# io_1.net
KiCad netlist of a schematic drawn in Altium Designer
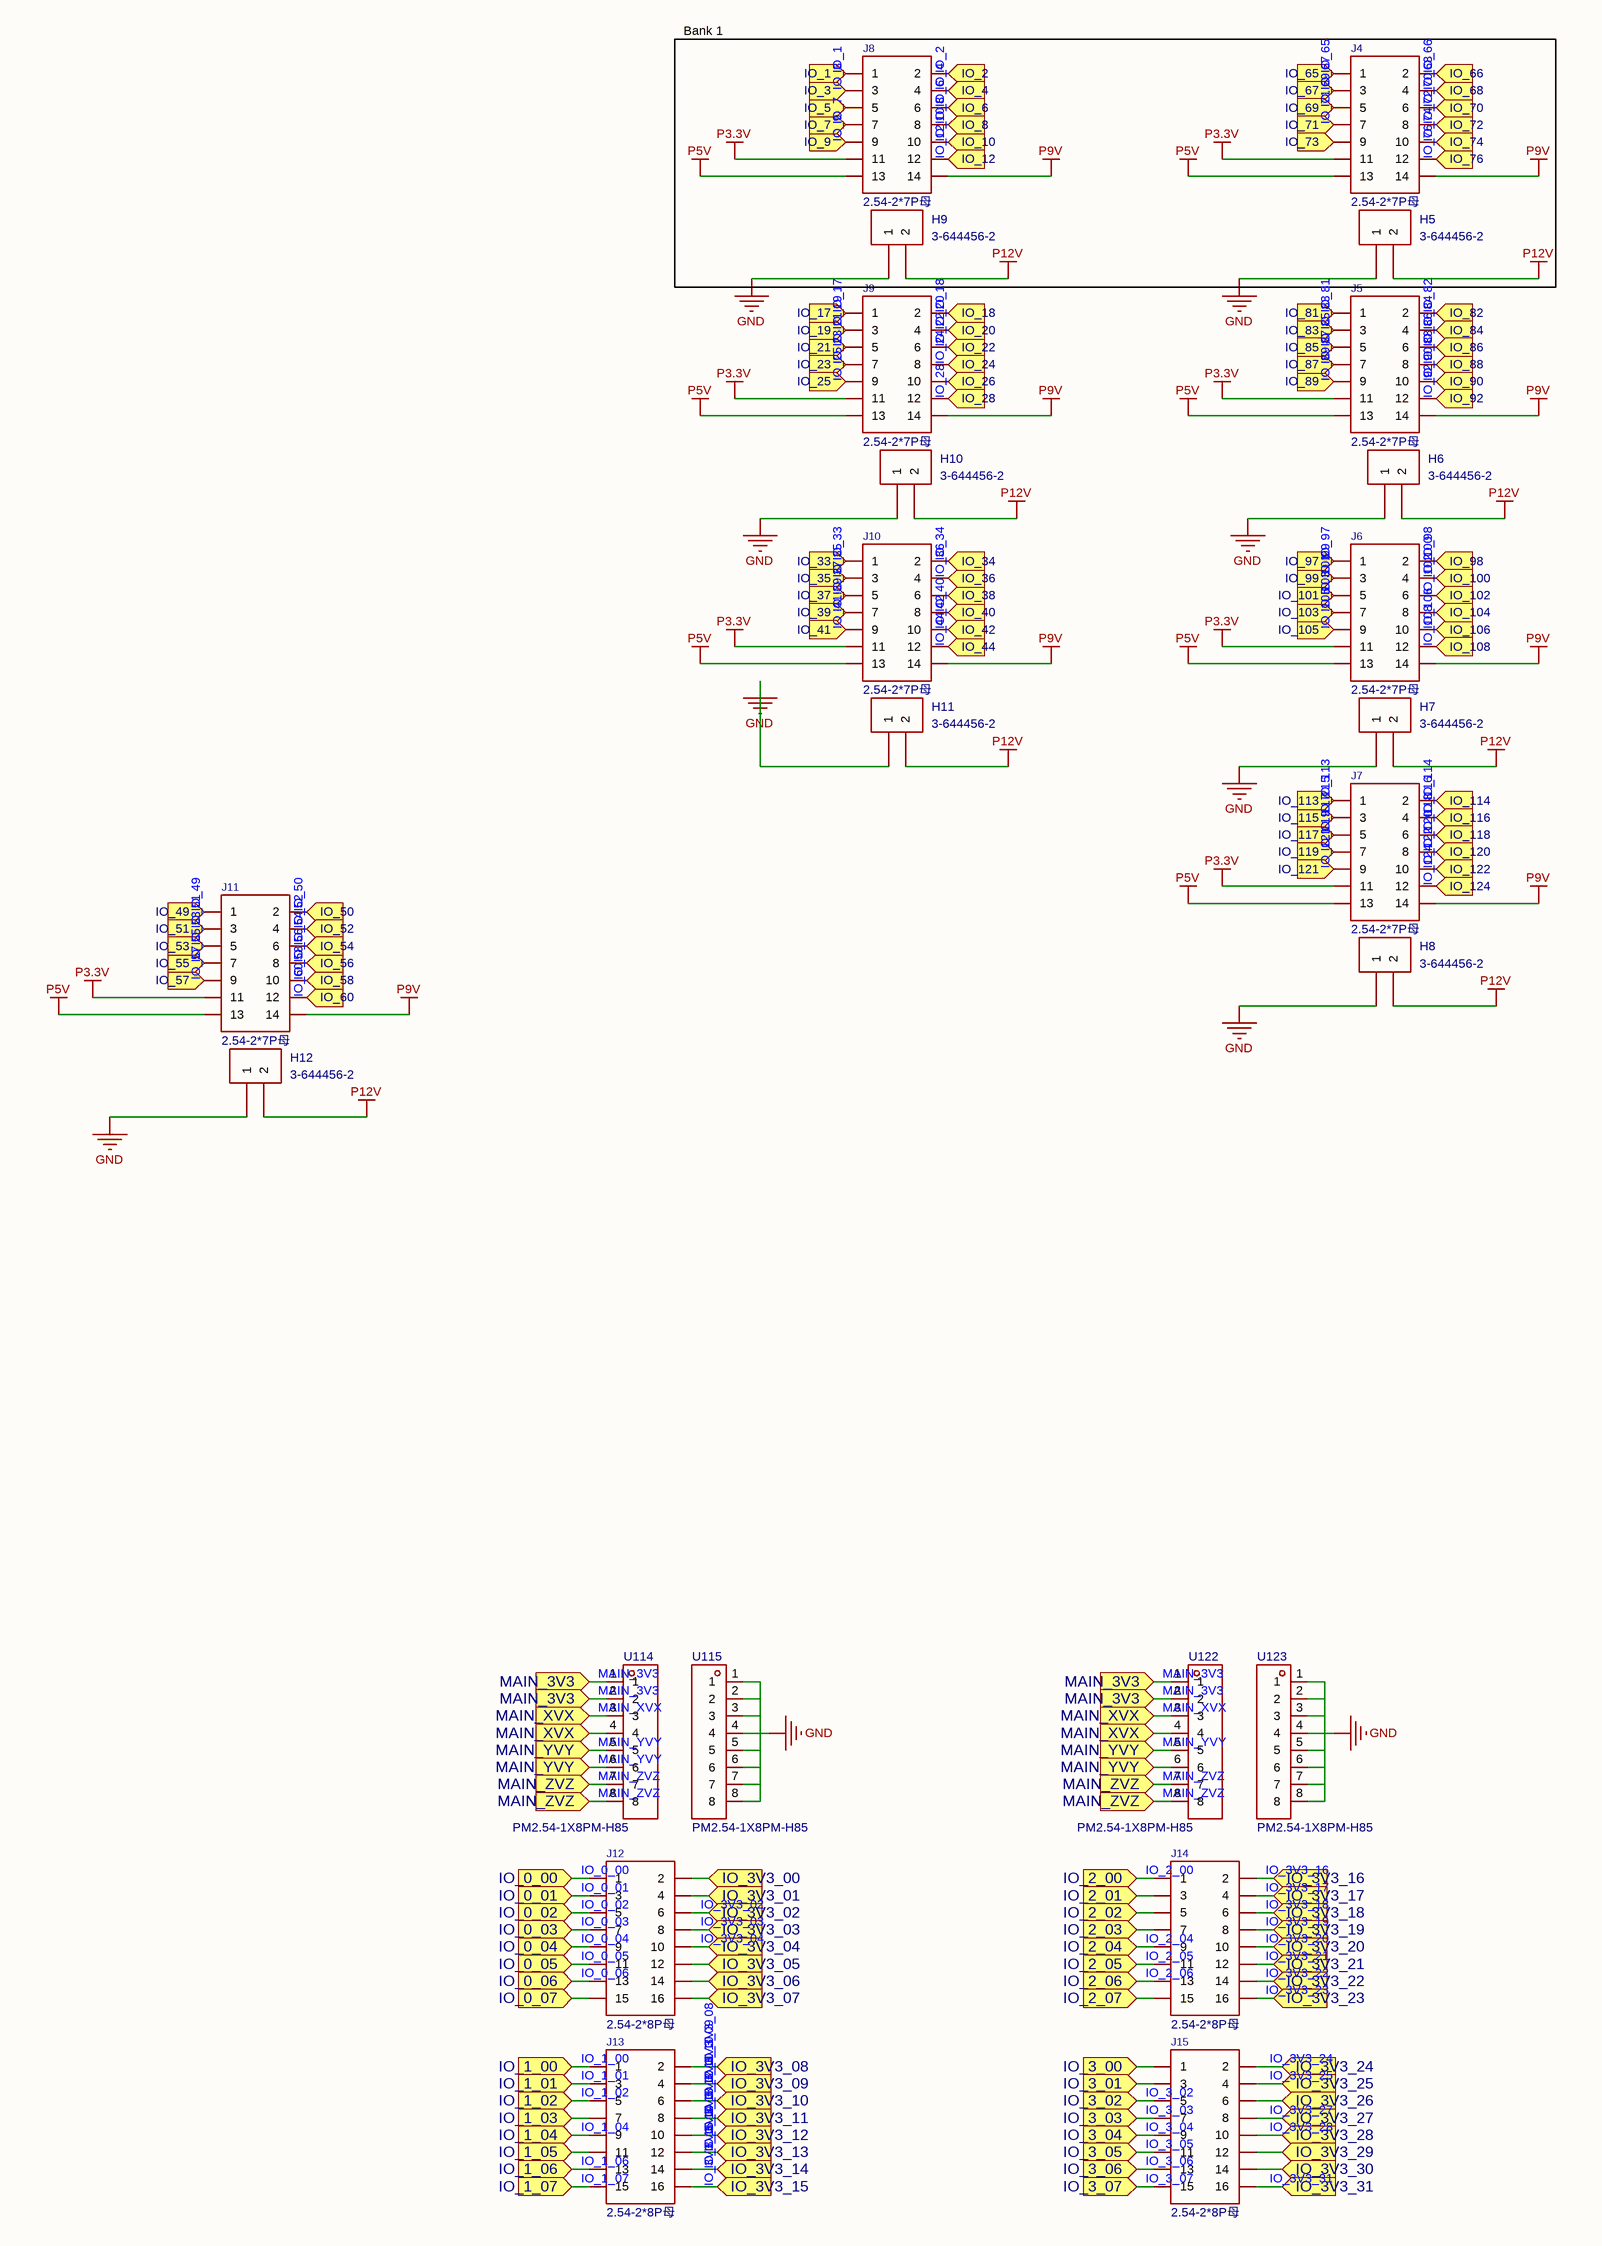
[diagram p0: io_1.schdoc]

(export (version "E")
  (design (tool "Eeschema 10.0.6"))
  (components
    (comp (ref "H5")
      (value "3-644456-2")
      (footprint "HDR-TH_2P-P2.54-V-M-1")
      (fields (field (name "MANUFACTURER") "TE Connectivity(泰科电子)"))
      (libsource (lib "altium-import") (part "root_1_3-644456-2_"))
    )
    (comp (ref "H6")
      (value "3-644456-2")
      (footprint "HDR-TH_2P-P2.54-V-M-1")
      (fields (field (name "MANUFACTURER") "TE Connectivity(泰科电子)"))
      (libsource (lib "altium-import") (part "root_1_3-644456-2_"))
    )
    (comp (ref "H7")
      (value "3-644456-2")
      (footprint "HDR-TH_2P-P2.54-V-M-1")
      (fields (field (name "MANUFACTURER") "TE Connectivity(泰科电子)"))
      (libsource (lib "altium-import") (part "root_1_3-644456-2_"))
    )
    (comp (ref "H8")
      (value "3-644456-2")
      (footprint "HDR-TH_2P-P2.54-V-M-1")
      (fields (field (name "MANUFACTURER") "TE Connectivity(泰科电子)"))
      (libsource (lib "altium-import") (part "root_1_3-644456-2_"))
    )
    (comp (ref "H9")
      (value "3-644456-2")
      (footprint "HDR-TH_2P-P2.54-V-M-1")
      (fields (field (name "MANUFACTURER") "TE Connectivity(泰科电子)"))
      (libsource (lib "altium-import") (part "root_1_3-644456-2_"))
    )
    (comp (ref "H10")
      (value "3-644456-2")
      (footprint "HDR-TH_2P-P2.54-V-M-1")
      (fields (field (name "MANUFACTURER") "TE Connectivity(泰科电子)"))
      (libsource (lib "altium-import") (part "root_1_3-644456-2_"))
    )
    (comp (ref "H11")
      (value "3-644456-2")
      (footprint "HDR-TH_2P-P2.54-V-M-1")
      (fields (field (name "MANUFACTURER") "TE Connectivity(泰科电子)"))
      (libsource (lib "altium-import") (part "root_1_3-644456-2_"))
    )
    (comp (ref "H12")
      (value "3-644456-2")
      (footprint "HDR-TH_2P-P2.54-V-M-1")
      (fields (field (name "MANUFACTURER") "TE Connectivity(泰科电子)"))
      (libsource (lib "altium-import") (part "root_1_3-644456-2_"))
    )
    (comp (ref "J4")
      (value "2.54-2*7P母")
      (footprint "HDR-TH_14P-P2.54-V-F-R2-C7-S2.54-1")
      (fields (field (name "MANUFACTURER") "BOOMELE(博穆精密)"))
      (libsource (lib "altium-import") (part "root_0_2.54-2*7P母_"))
    )
    (comp (ref "J5")
      (value "2.54-2*7P母")
      (footprint "HDR-TH_14P-P2.54-V-F-R2-C7-S2.54-1")
      (fields (field (name "MANUFACTURER") "BOOMELE(博穆精密)"))
      (libsource (lib "altium-import") (part "root_0_2.54-2*7P母_"))
    )
    (comp (ref "J6")
      (value "2.54-2*7P母")
      (footprint "HDR-TH_14P-P2.54-V-F-R2-C7-S2.54-1")
      (fields (field (name "MANUFACTURER") "BOOMELE(博穆精密)"))
      (libsource (lib "altium-import") (part "root_0_2.54-2*7P母_"))
    )
    (comp (ref "J7")
      (value "2.54-2*7P母")
      (footprint "HDR-TH_14P-P2.54-V-F-R2-C7-S2.54-1")
      (fields (field (name "MANUFACTURER") "BOOMELE(博穆精密)"))
      (libsource (lib "altium-import") (part "root_0_2.54-2*7P母_"))
    )
    (comp (ref "J8")
      (value "2.54-2*7P母")
      (footprint "HDR-TH_14P-P2.54-V-F-R2-C7-S2.54-1")
      (fields (field (name "MANUFACTURER") "BOOMELE(博穆精密)"))
      (libsource (lib "altium-import") (part "root_0_2.54-2*7P母_"))
    )
    (comp (ref "J9")
      (value "2.54-2*7P母")
      (footprint "HDR-TH_14P-P2.54-V-F-R2-C7-S2.54-1")
      (fields (field (name "MANUFACTURER") "BOOMELE(博穆精密)"))
      (libsource (lib "altium-import") (part "root_0_2.54-2*7P母_"))
    )
    (comp (ref "J10")
      (value "2.54-2*7P母")
      (footprint "HDR-TH_14P-P2.54-V-F-R2-C7-S2.54-1")
      (fields (field (name "MANUFACTURER") "BOOMELE(博穆精密)"))
      (libsource (lib "altium-import") (part "root_0_2.54-2*7P母_"))
    )
    (comp (ref "J11")
      (value "2.54-2*7P母")
      (footprint "HDR-TH_14P-P2.54-V-F-R2-C7-S2.54-1")
      (fields (field (name "MANUFACTURER") "BOOMELE(博穆精密)"))
      (libsource (lib "altium-import") (part "root_0_2.54-2*7P母_"))
    )
    (comp (ref "J12")
      (value "2.54-2*8P母")
      (footprint "HDR-TH_16P-P2.54-V-F-R2-C8-S2.54")
      (fields (field (name "MANUFACTURER") "BOOMELE(博穆精密)"))
      (libsource (lib "altium-import") (part "root_0_2.54-2*8P母_"))
    )
    (comp (ref "J13")
      (value "2.54-2*8P母")
      (footprint "HDR-TH_16P-P2.54-V-F-R2-C8-S2.54")
      (fields (field (name "MANUFACTURER") "BOOMELE(博穆精密)"))
      (libsource (lib "altium-import") (part "root_0_2.54-2*8P母_"))
    )
    (comp (ref "J14")
      (value "2.54-2*8P母")
      (footprint "HDR-TH_16P-P2.54-V-F-R2-C8-S2.54")
      (fields (field (name "MANUFACTURER") "BOOMELE(博穆精密)"))
      (libsource (lib "altium-import") (part "root_0_2.54-2*8P母_"))
    )
    (comp (ref "J15")
      (value "2.54-2*8P母")
      (footprint "HDR-TH_16P-P2.54-V-F-R2-C8-S2.54")
      (fields (field (name "MANUFACTURER") "BOOMELE(博穆精密)"))
      (libsource (lib "altium-import") (part "root_0_2.54-2*8P母_"))
    )
    (comp (ref "U114")
      (value "PM2.54-1X8PM-H85")
      (footprint "HDR-TH_8P-P2.54-V-F")
      (fields (field (name "MANUFACTURER") "JXTCONN(聚兴泰)"))
      (libsource (lib "altium-import") (part "root_0_PM2.54-1X8PM-H85_"))
    )
    (comp (ref "U115")
      (value "PM2.54-1X8PM-H85")
      (footprint "HDR-TH_8P-P2.54-V-F")
      (fields (field (name "MANUFACTURER") "JXTCONN(聚兴泰)"))
      (libsource (lib "altium-import") (part "root_0_mirrored_PM2.54-1X8PM-H85_"))
    )
    (comp (ref "U122")
      (value "PM2.54-1X8PM-H85")
      (footprint "HDR-TH_8P-P2.54-V-F")
      (fields (field (name "MANUFACTURER") "JXTCONN(聚兴泰)"))
      (libsource (lib "altium-import") (part "root_0_PM2.54-1X8PM-H85_"))
    )
    (comp (ref "U123")
      (value "PM2.54-1X8PM-H85")
      (footprint "HDR-TH_8P-P2.54-V-F")
      (fields (field (name "MANUFACTURER") "JXTCONN(聚兴泰)"))
      (libsource (lib "altium-import") (part "root_0_mirrored_PM2.54-1X8PM-H85_"))
    )
  )
  (nets
    (net (code "1") (name "/IO_0_00") (class "Default")
      (node (ref "J12") (pin "1") (pinfunction "1_1") (pintype "passive"))
    )
    (net (code "2") (name "/IO_0_01") (class "Default")
      (node (ref "J12") (pin "3") (pinfunction "3_3") (pintype "passive"))
    )
    (net (code "3") (name "/IO_0_02") (class "Default")
      (node (ref "J12") (pin "5") (pinfunction "5_5") (pintype "passive"))
    )
    (net (code "4") (name "/IO_0_03") (class "Default")
      (node (ref "J12") (pin "7") (pinfunction "7_7") (pintype "passive"))
    )
    (net (code "5") (name "/IO_0_04") (class "Default")
      (node (ref "J12") (pin "9") (pinfunction "9_9") (pintype "passive"))
    )
    (net (code "6") (name "/IO_0_05") (class "Default")
      (node (ref "J12") (pin "11") (pinfunction "11_11") (pintype "passive"))
    )
    (net (code "7") (name "/IO_0_06") (class "Default")
      (node (ref "J12") (pin "13") (pinfunction "13_13") (pintype "passive"))
    )
    (net (code "8") (name "/IO_0_07") (class "Default")
      (node (ref "J12") (pin "15") (pinfunction "15_15") (pintype "passive"))
    )
    (net (code "9") (name "/IO_1") (class "Default")
      (node (ref "J8") (pin "1") (pinfunction "1_1") (pintype "passive"))
    )
    (net (code "10") (name "/IO_1_00") (class "Default")
      (node (ref "J13") (pin "1") (pinfunction "1_1") (pintype "passive"))
    )
    (net (code "11") (name "/IO_1_01") (class "Default")
      (node (ref "J13") (pin "3") (pinfunction "3_3") (pintype "passive"))
    )
    (net (code "12") (name "/IO_1_02") (class "Default")
      (node (ref "J13") (pin "5") (pinfunction "5_5") (pintype "passive"))
    )
    (net (code "13") (name "/IO_1_03") (class "Default")
      (node (ref "J13") (pin "7") (pinfunction "7_7") (pintype "passive"))
    )
    (net (code "14") (name "/IO_1_04") (class "Default")
      (node (ref "J13") (pin "9") (pinfunction "9_9") (pintype "passive"))
    )
    (net (code "15") (name "/IO_1_05") (class "Default")
      (node (ref "J13") (pin "11") (pinfunction "11_11") (pintype "passive"))
    )
    (net (code "16") (name "/IO_1_06") (class "Default")
      (node (ref "J13") (pin "13") (pinfunction "13_13") (pintype "passive"))
    )
    (net (code "17") (name "/IO_1_07") (class "Default")
      (node (ref "J13") (pin "15") (pinfunction "15_15") (pintype "passive"))
    )
    (net (code "18") (name "/IO_2") (class "Default")
      (node (ref "J8") (pin "2") (pinfunction "2_2") (pintype "passive"))
    )
    (net (code "19") (name "/IO_2_00") (class "Default")
      (node (ref "J14") (pin "1") (pinfunction "1_1") (pintype "passive"))
    )
    (net (code "20") (name "/IO_2_01") (class "Default")
      (node (ref "J14") (pin "3") (pinfunction "3_3") (pintype "passive"))
    )
    (net (code "21") (name "/IO_2_02") (class "Default")
      (node (ref "J14") (pin "5") (pinfunction "5_5") (pintype "passive"))
    )
    (net (code "22") (name "/IO_2_03") (class "Default")
      (node (ref "J14") (pin "7") (pinfunction "7_7") (pintype "passive"))
    )
    (net (code "23") (name "/IO_2_04") (class "Default")
      (node (ref "J14") (pin "9") (pinfunction "9_9") (pintype "passive"))
    )
    (net (code "24") (name "/IO_2_05") (class "Default")
      (node (ref "J14") (pin "11") (pinfunction "11_11") (pintype "passive"))
    )
    (net (code "25") (name "/IO_2_06") (class "Default")
      (node (ref "J14") (pin "13") (pinfunction "13_13") (pintype "passive"))
    )
    (net (code "26") (name "/IO_2_07") (class "Default")
      (node (ref "J14") (pin "15") (pinfunction "15_15") (pintype "passive"))
    )
    (net (code "27") (name "/IO_3") (class "Default")
      (node (ref "J8") (pin "3") (pinfunction "3_3") (pintype "passive"))
    )
    (net (code "28") (name "/IO_3V3_00") (class "Default")
      (node (ref "J12") (pin "2") (pinfunction "2_2") (pintype "passive"))
    )
    (net (code "29") (name "/IO_3V3_01") (class "Default")
      (node (ref "J12") (pin "4") (pinfunction "4_4") (pintype "passive"))
    )
    (net (code "30") (name "/IO_3V3_02") (class "Default")
      (node (ref "J12") (pin "6") (pinfunction "6_6") (pintype "passive"))
    )
    (net (code "31") (name "/IO_3V3_03") (class "Default")
      (node (ref "J12") (pin "8") (pinfunction "8_8") (pintype "passive"))
    )
    (net (code "32") (name "/IO_3V3_04") (class "Default")
      (node (ref "J12") (pin "10") (pinfunction "10_10") (pintype "passive"))
    )
    (net (code "33") (name "/IO_3V3_05") (class "Default")
      (node (ref "J12") (pin "12") (pinfunction "12_12") (pintype "passive"))
    )
    (net (code "34") (name "/IO_3V3_06") (class "Default")
      (node (ref "J12") (pin "14") (pinfunction "14_14") (pintype "passive"))
    )
    (net (code "35") (name "/IO_3V3_07") (class "Default")
      (node (ref "J12") (pin "16") (pinfunction "16_16") (pintype "passive"))
    )
    (net (code "36") (name "/IO_3V3_08") (class "Default")
      (node (ref "J13") (pin "2") (pinfunction "2_2") (pintype "passive"))
    )
    (net (code "37") (name "/IO_3V3_09") (class "Default")
      (node (ref "J13") (pin "4") (pinfunction "4_4") (pintype "passive"))
    )
    (net (code "38") (name "/IO_3V3_10") (class "Default")
      (node (ref "J13") (pin "6") (pinfunction "6_6") (pintype "passive"))
    )
    (net (code "39") (name "/IO_3V3_11") (class "Default")
      (node (ref "J13") (pin "8") (pinfunction "8_8") (pintype "passive"))
    )
    (net (code "40") (name "/IO_3V3_12") (class "Default")
      (node (ref "J13") (pin "10") (pinfunction "10_10") (pintype "passive"))
    )
    (net (code "41") (name "/IO_3V3_13") (class "Default")
      (node (ref "J13") (pin "12") (pinfunction "12_12") (pintype "passive"))
    )
    (net (code "42") (name "/IO_3V3_14") (class "Default")
      (node (ref "J13") (pin "14") (pinfunction "14_14") (pintype "passive"))
    )
    (net (code "43") (name "/IO_3V3_15") (class "Default")
      (node (ref "J13") (pin "16") (pinfunction "16_16") (pintype "passive"))
    )
    (net (code "44") (name "/IO_3V3_16") (class "Default")
      (node (ref "J14") (pin "2") (pinfunction "2_2") (pintype "passive"))
    )
    (net (code "45") (name "/IO_3V3_17") (class "Default")
      (node (ref "J14") (pin "4") (pinfunction "4_4") (pintype "passive"))
    )
    (net (code "46") (name "/IO_3V3_18") (class "Default")
      (node (ref "J14") (pin "6") (pinfunction "6_6") (pintype "passive"))
    )
    (net (code "47") (name "/IO_3V3_19") (class "Default")
      (node (ref "J14") (pin "8") (pinfunction "8_8") (pintype "passive"))
    )
    (net (code "48") (name "/IO_3V3_20") (class "Default")
      (node (ref "J14") (pin "10") (pinfunction "10_10") (pintype "passive"))
    )
    (net (code "49") (name "/IO_3V3_21") (class "Default")
      (node (ref "J14") (pin "12") (pinfunction "12_12") (pintype "passive"))
    )
    (net (code "50") (name "/IO_3V3_22") (class "Default")
      (node (ref "J14") (pin "14") (pinfunction "14_14") (pintype "passive"))
    )
    (net (code "51") (name "/IO_3V3_23") (class "Default")
      (node (ref "J14") (pin "16") (pinfunction "16_16") (pintype "passive"))
    )
    (net (code "52") (name "/IO_3V3_24") (class "Default")
      (node (ref "J15") (pin "2") (pinfunction "2_2") (pintype "passive"))
    )
    (net (code "53") (name "/IO_3V3_25") (class "Default")
      (node (ref "J15") (pin "4") (pinfunction "4_4") (pintype "passive"))
    )
    (net (code "54") (name "/IO_3V3_26") (class "Default")
      (node (ref "J15") (pin "6") (pinfunction "6_6") (pintype "passive"))
    )
    (net (code "55") (name "/IO_3V3_27") (class "Default")
      (node (ref "J15") (pin "8") (pinfunction "8_8") (pintype "passive"))
    )
    (net (code "56") (name "/IO_3V3_28") (class "Default")
      (node (ref "J15") (pin "10") (pinfunction "10_10") (pintype "passive"))
    )
    (net (code "57") (name "/IO_3V3_29") (class "Default")
      (node (ref "J15") (pin "12") (pinfunction "12_12") (pintype "passive"))
    )
    (net (code "58") (name "/IO_3V3_30") (class "Default")
      (node (ref "J15") (pin "14") (pinfunction "14_14") (pintype "passive"))
    )
    (net (code "59") (name "/IO_3V3_31") (class "Default")
      (node (ref "J15") (pin "16") (pinfunction "16_16") (pintype "passive"))
    )
    (net (code "60") (name "/IO_3_00") (class "Default")
      (node (ref "J15") (pin "1") (pinfunction "1_1") (pintype "passive"))
    )
    (net (code "61") (name "/IO_3_01") (class "Default")
      (node (ref "J15") (pin "3") (pinfunction "3_3") (pintype "passive"))
    )
    (net (code "62") (name "/IO_3_02") (class "Default")
      (node (ref "J15") (pin "5") (pinfunction "5_5") (pintype "passive"))
    )
    (net (code "63") (name "/IO_3_03") (class "Default")
      (node (ref "J15") (pin "7") (pinfunction "7_7") (pintype "passive"))
    )
    (net (code "64") (name "/IO_3_04") (class "Default")
      (node (ref "J15") (pin "9") (pinfunction "9_9") (pintype "passive"))
    )
    (net (code "65") (name "/IO_3_05") (class "Default")
      (node (ref "J15") (pin "11") (pinfunction "11_11") (pintype "passive"))
    )
    (net (code "66") (name "/IO_3_06") (class "Default")
      (node (ref "J15") (pin "13") (pinfunction "13_13") (pintype "passive"))
    )
    (net (code "67") (name "/IO_3_07") (class "Default")
      (node (ref "J15") (pin "15") (pinfunction "15_15") (pintype "passive"))
    )
    (net (code "68") (name "/IO_4") (class "Default")
      (node (ref "J8") (pin "4") (pinfunction "4_4") (pintype "passive"))
    )
    (net (code "69") (name "/IO_5") (class "Default")
      (node (ref "J8") (pin "5") (pinfunction "5_5") (pintype "passive"))
    )
    (net (code "70") (name "/IO_6") (class "Default")
      (node (ref "J8") (pin "6") (pinfunction "6_6") (pintype "passive"))
    )
    (net (code "71") (name "/IO_7") (class "Default")
      (node (ref "J8") (pin "7") (pinfunction "7_7") (pintype "passive"))
    )
    (net (code "72") (name "/IO_8") (class "Default")
      (node (ref "J8") (pin "8") (pinfunction "8_8") (pintype "passive"))
    )
    (net (code "73") (name "/IO_9") (class "Default")
      (node (ref "J8") (pin "9") (pinfunction "9_9") (pintype "passive"))
    )
    (net (code "74") (name "/IO_10") (class "Default")
      (node (ref "J8") (pin "10") (pinfunction "10_10") (pintype "passive"))
    )
    (net (code "75") (name "/IO_12") (class "Default")
      (node (ref "J8") (pin "12") (pinfunction "12_12") (pintype "passive"))
    )
    (net (code "76") (name "/IO_17") (class "Default")
      (node (ref "J9") (pin "1") (pinfunction "1_1") (pintype "passive"))
    )
    (net (code "77") (name "/IO_18") (class "Default")
      (node (ref "J9") (pin "2") (pinfunction "2_2") (pintype "passive"))
    )
    (net (code "78") (name "/IO_19") (class "Default")
      (node (ref "J9") (pin "3") (pinfunction "3_3") (pintype "passive"))
    )
    (net (code "79") (name "/IO_20") (class "Default")
      (node (ref "J9") (pin "4") (pinfunction "4_4") (pintype "passive"))
    )
    (net (code "80") (name "/IO_21") (class "Default")
      (node (ref "J9") (pin "5") (pinfunction "5_5") (pintype "passive"))
    )
    (net (code "81") (name "/IO_22") (class "Default")
      (node (ref "J9") (pin "6") (pinfunction "6_6") (pintype "passive"))
    )
    (net (code "82") (name "/IO_23") (class "Default")
      (node (ref "J9") (pin "7") (pinfunction "7_7") (pintype "passive"))
    )
    (net (code "83") (name "/IO_24") (class "Default")
      (node (ref "J9") (pin "8") (pinfunction "8_8") (pintype "passive"))
    )
    (net (code "84") (name "/IO_25") (class "Default")
      (node (ref "J9") (pin "9") (pinfunction "9_9") (pintype "passive"))
    )
    (net (code "85") (name "/IO_26") (class "Default")
      (node (ref "J9") (pin "10") (pinfunction "10_10") (pintype "passive"))
    )
    (net (code "86") (name "/IO_28") (class "Default")
      (node (ref "J9") (pin "12") (pinfunction "12_12") (pintype "passive"))
    )
    (net (code "87") (name "/IO_33") (class "Default")
      (node (ref "J10") (pin "1") (pinfunction "1_1") (pintype "passive"))
    )
    (net (code "88") (name "/IO_34") (class "Default")
      (node (ref "J10") (pin "2") (pinfunction "2_2") (pintype "passive"))
    )
    (net (code "89") (name "/IO_35") (class "Default")
      (node (ref "J10") (pin "3") (pinfunction "3_3") (pintype "passive"))
    )
    (net (code "90") (name "/IO_36") (class "Default")
      (node (ref "J10") (pin "4") (pinfunction "4_4") (pintype "passive"))
    )
    (net (code "91") (name "/IO_37") (class "Default")
      (node (ref "J10") (pin "5") (pinfunction "5_5") (pintype "passive"))
    )
    (net (code "92") (name "/IO_38") (class "Default")
      (node (ref "J10") (pin "6") (pinfunction "6_6") (pintype "passive"))
    )
    (net (code "93") (name "/IO_39") (class "Default")
      (node (ref "J10") (pin "7") (pinfunction "7_7") (pintype "passive"))
    )
    (net (code "94") (name "/IO_40") (class "Default")
      (node (ref "J10") (pin "8") (pinfunction "8_8") (pintype "passive"))
    )
    (net (code "95") (name "/IO_41") (class "Default")
      (node (ref "J10") (pin "9") (pinfunction "9_9") (pintype "passive"))
    )
    (net (code "96") (name "/IO_42") (class "Default")
      (node (ref "J10") (pin "10") (pinfunction "10_10") (pintype "passive"))
    )
    (net (code "97") (name "/IO_44") (class "Default")
      (node (ref "J10") (pin "12") (pinfunction "12_12") (pintype "passive"))
    )
    (net (code "98") (name "/IO_49") (class "Default")
      (node (ref "J11") (pin "1") (pinfunction "1_1") (pintype "passive"))
    )
    (net (code "99") (name "/IO_50") (class "Default")
      (node (ref "J11") (pin "2") (pinfunction "2_2") (pintype "passive"))
    )
    (net (code "100") (name "/IO_51") (class "Default")
      (node (ref "J11") (pin "3") (pinfunction "3_3") (pintype "passive"))
    )
    (net (code "101") (name "/IO_52") (class "Default")
      (node (ref "J11") (pin "4") (pinfunction "4_4") (pintype "passive"))
    )
    (net (code "102") (name "/IO_53") (class "Default")
      (node (ref "J11") (pin "5") (pinfunction "5_5") (pintype "passive"))
    )
    (net (code "103") (name "/IO_54") (class "Default")
      (node (ref "J11") (pin "6") (pinfunction "6_6") (pintype "passive"))
    )
    (net (code "104") (name "/IO_55") (class "Default")
      (node (ref "J11") (pin "7") (pinfunction "7_7") (pintype "passive"))
    )
    (net (code "105") (name "/IO_56") (class "Default")
      (node (ref "J11") (pin "8") (pinfunction "8_8") (pintype "passive"))
    )
    (net (code "106") (name "/IO_57") (class "Default")
      (node (ref "J11") (pin "9") (pinfunction "9_9") (pintype "passive"))
    )
    (net (code "107") (name "/IO_58") (class "Default")
      (node (ref "J11") (pin "10") (pinfunction "10_10") (pintype "passive"))
    )
    (net (code "108") (name "/IO_60") (class "Default")
      (node (ref "J11") (pin "12") (pinfunction "12_12") (pintype "passive"))
    )
    (net (code "109") (name "/IO_65") (class "Default")
      (node (ref "J4") (pin "1") (pinfunction "1_1") (pintype "passive"))
    )
    (net (code "110") (name "/IO_66") (class "Default")
      (node (ref "J4") (pin "2") (pinfunction "2_2") (pintype "passive"))
    )
    (net (code "111") (name "/IO_67") (class "Default")
      (node (ref "J4") (pin "3") (pinfunction "3_3") (pintype "passive"))
    )
    (net (code "112") (name "/IO_68") (class "Default")
      (node (ref "J4") (pin "4") (pinfunction "4_4") (pintype "passive"))
    )
    (net (code "113") (name "/IO_69") (class "Default")
      (node (ref "J4") (pin "5") (pinfunction "5_5") (pintype "passive"))
    )
    (net (code "114") (name "/IO_70") (class "Default")
      (node (ref "J4") (pin "6") (pinfunction "6_6") (pintype "passive"))
    )
    (net (code "115") (name "/IO_71") (class "Default")
      (node (ref "J4") (pin "7") (pinfunction "7_7") (pintype "passive"))
    )
    (net (code "116") (name "/IO_72") (class "Default")
      (node (ref "J4") (pin "8") (pinfunction "8_8") (pintype "passive"))
    )
    (net (code "117") (name "/IO_73") (class "Default")
      (node (ref "J4") (pin "9") (pinfunction "9_9") (pintype "passive"))
    )
    (net (code "118") (name "/IO_74") (class "Default")
      (node (ref "J4") (pin "10") (pinfunction "10_10") (pintype "passive"))
    )
    (net (code "119") (name "/IO_76") (class "Default")
      (node (ref "J4") (pin "12") (pinfunction "12_12") (pintype "passive"))
    )
    (net (code "120") (name "/IO_81") (class "Default")
      (node (ref "J5") (pin "1") (pinfunction "1_1") (pintype "passive"))
    )
    (net (code "121") (name "/IO_82") (class "Default")
      (node (ref "J5") (pin "2") (pinfunction "2_2") (pintype "passive"))
    )
    (net (code "122") (name "/IO_83") (class "Default")
      (node (ref "J5") (pin "3") (pinfunction "3_3") (pintype "passive"))
    )
    (net (code "123") (name "/IO_84") (class "Default")
      (node (ref "J5") (pin "4") (pinfunction "4_4") (pintype "passive"))
    )
    (net (code "124") (name "/IO_85") (class "Default")
      (node (ref "J5") (pin "5") (pinfunction "5_5") (pintype "passive"))
    )
    (net (code "125") (name "/IO_86") (class "Default")
      (node (ref "J5") (pin "6") (pinfunction "6_6") (pintype "passive"))
    )
    (net (code "126") (name "/IO_87") (class "Default")
      (node (ref "J5") (pin "7") (pinfunction "7_7") (pintype "passive"))
    )
    (net (code "127") (name "/IO_88") (class "Default")
      (node (ref "J5") (pin "8") (pinfunction "8_8") (pintype "passive"))
    )
    (net (code "128") (name "/IO_89") (class "Default")
      (node (ref "J5") (pin "9") (pinfunction "9_9") (pintype "passive"))
    )
    (net (code "129") (name "/IO_90") (class "Default")
      (node (ref "J5") (pin "10") (pinfunction "10_10") (pintype "passive"))
    )
    (net (code "130") (name "/IO_92") (class "Default")
      (node (ref "J5") (pin "12") (pinfunction "12_12") (pintype "passive"))
    )
    (net (code "131") (name "/IO_97") (class "Default")
      (node (ref "J6") (pin "1") (pinfunction "1_1") (pintype "passive"))
    )
    (net (code "132") (name "/IO_98") (class "Default")
      (node (ref "J6") (pin "2") (pinfunction "2_2") (pintype "passive"))
    )
    (net (code "133") (name "/IO_99") (class "Default")
      (node (ref "J6") (pin "3") (pinfunction "3_3") (pintype "passive"))
    )
    (net (code "134") (name "/IO_100") (class "Default")
      (node (ref "J6") (pin "4") (pinfunction "4_4") (pintype "passive"))
    )
    (net (code "135") (name "/IO_101") (class "Default")
      (node (ref "J6") (pin "5") (pinfunction "5_5") (pintype "passive"))
    )
    (net (code "136") (name "/IO_102") (class "Default")
      (node (ref "J6") (pin "6") (pinfunction "6_6") (pintype "passive"))
    )
    (net (code "137") (name "/IO_103") (class "Default")
      (node (ref "J6") (pin "7") (pinfunction "7_7") (pintype "passive"))
    )
    (net (code "138") (name "/IO_104") (class "Default")
      (node (ref "J6") (pin "8") (pinfunction "8_8") (pintype "passive"))
    )
    (net (code "139") (name "/IO_105") (class "Default")
      (node (ref "J6") (pin "9") (pinfunction "9_9") (pintype "passive"))
    )
    (net (code "140") (name "/IO_106") (class "Default")
      (node (ref "J6") (pin "10") (pinfunction "10_10") (pintype "passive"))
    )
    (net (code "141") (name "/IO_108") (class "Default")
      (node (ref "J6") (pin "12") (pinfunction "12_12") (pintype "passive"))
    )
    (net (code "142") (name "/IO_113") (class "Default")
      (node (ref "J7") (pin "1") (pinfunction "1_1") (pintype "passive"))
    )
    (net (code "143") (name "/IO_114") (class "Default")
      (node (ref "J7") (pin "2") (pinfunction "2_2") (pintype "passive"))
    )
    (net (code "144") (name "/IO_115") (class "Default")
      (node (ref "J7") (pin "3") (pinfunction "3_3") (pintype "passive"))
    )
    (net (code "145") (name "/IO_116") (class "Default")
      (node (ref "J7") (pin "4") (pinfunction "4_4") (pintype "passive"))
    )
    (net (code "146") (name "/IO_117") (class "Default")
      (node (ref "J7") (pin "5") (pinfunction "5_5") (pintype "passive"))
    )
    (net (code "147") (name "/IO_118") (class "Default")
      (node (ref "J7") (pin "6") (pinfunction "6_6") (pintype "passive"))
    )
    (net (code "148") (name "/IO_119") (class "Default")
      (node (ref "J7") (pin "7") (pinfunction "7_7") (pintype "passive"))
    )
    (net (code "149") (name "/IO_120") (class "Default")
      (node (ref "J7") (pin "8") (pinfunction "8_8") (pintype "passive"))
    )
    (net (code "150") (name "/IO_121") (class "Default")
      (node (ref "J7") (pin "9") (pinfunction "9_9") (pintype "passive"))
    )
    (net (code "151") (name "/IO_122") (class "Default")
      (node (ref "J7") (pin "10") (pinfunction "10_10") (pintype "passive"))
    )
    (net (code "152") (name "/IO_124") (class "Default")
      (node (ref "J7") (pin "12") (pinfunction "12_12") (pintype "passive"))
    )
    (net (code "153") (name "/MAIN_3V3") (class "Default")
      (node (ref "U114") (pin "1") (pinfunction "1_1") (pintype "passive"))
      (node (ref "U114") (pin "2") (pinfunction "2_2") (pintype "passive"))
      (node (ref "U122") (pin "1") (pinfunction "1_1") (pintype "passive"))
      (node (ref "U122") (pin "2") (pinfunction "2_2") (pintype "passive"))
    )
    (net (code "154") (name "/MAIN_XVX") (class "Default")
      (node (ref "U114") (pin "3") (pinfunction "3_3") (pintype "passive"))
      (node (ref "U114") (pin "4") (pinfunction "4_4") (pintype "passive"))
      (node (ref "U122") (pin "3") (pinfunction "3_3") (pintype "passive"))
      (node (ref "U122") (pin "4") (pinfunction "4_4") (pintype "passive"))
    )
    (net (code "155") (name "/MAIN_YVY") (class "Default")
      (node (ref "U114") (pin "5") (pinfunction "5_5") (pintype "passive"))
      (node (ref "U114") (pin "6") (pinfunction "6_6") (pintype "passive"))
      (node (ref "U122") (pin "5") (pinfunction "5_5") (pintype "passive"))
      (node (ref "U122") (pin "6") (pinfunction "6_6") (pintype "passive"))
    )
    (net (code "156") (name "/MAIN_ZVZ") (class "Default")
      (node (ref "U114") (pin "7") (pinfunction "7_7") (pintype "passive"))
      (node (ref "U114") (pin "8") (pinfunction "8_8") (pintype "passive"))
      (node (ref "U122") (pin "7") (pinfunction "7_7") (pintype "passive"))
      (node (ref "U122") (pin "8") (pinfunction "8_8") (pintype "passive"))
    )
    (net (code "157") (name "GND") (class "Default")
      (node (ref "H10") (pin "1") (pinfunction "1_1") (pintype "passive"))
      (node (ref "H11") (pin "1") (pinfunction "1_1") (pintype "passive"))
      (node (ref "H12") (pin "1") (pinfunction "1_1") (pintype "passive"))
      (node (ref "H5") (pin "1") (pinfunction "1_1") (pintype "passive"))
      (node (ref "H6") (pin "1") (pinfunction "1_1") (pintype "passive"))
      (node (ref "H7") (pin "1") (pinfunction "1_1") (pintype "passive"))
      (node (ref "H8") (pin "1") (pinfunction "1_1") (pintype "passive"))
      (node (ref "H9") (pin "1") (pinfunction "1_1") (pintype "passive"))
      (node (ref "U115") (pin "1") (pinfunction "1_1") (pintype "passive"))
      (node (ref "U115") (pin "2") (pinfunction "2_2") (pintype "passive"))
      (node (ref "U115") (pin "3") (pinfunction "3_3") (pintype "passive"))
      (node (ref "U115") (pin "4") (pinfunction "4_4") (pintype "passive"))
      (node (ref "U115") (pin "5") (pinfunction "5_5") (pintype "passive"))
      (node (ref "U115") (pin "6") (pinfunction "6_6") (pintype "passive"))
      (node (ref "U115") (pin "7") (pinfunction "7_7") (pintype "passive"))
      (node (ref "U115") (pin "8") (pinfunction "8_8") (pintype "passive"))
      (node (ref "U123") (pin "1") (pinfunction "1_1") (pintype "passive"))
      (node (ref "U123") (pin "2") (pinfunction "2_2") (pintype "passive"))
      (node (ref "U123") (pin "3") (pinfunction "3_3") (pintype "passive"))
      (node (ref "U123") (pin "4") (pinfunction "4_4") (pintype "passive"))
      (node (ref "U123") (pin "5") (pinfunction "5_5") (pintype "passive"))
      (node (ref "U123") (pin "6") (pinfunction "6_6") (pintype "passive"))
      (node (ref "U123") (pin "7") (pinfunction "7_7") (pintype "passive"))
      (node (ref "U123") (pin "8") (pinfunction "8_8") (pintype "passive"))
    )
    (net (code "158") (name "P3.3V") (class "Default")
      (node (ref "J10") (pin "11") (pinfunction "11_11") (pintype "passive"))
      (node (ref "J11") (pin "11") (pinfunction "11_11") (pintype "passive"))
      (node (ref "J4") (pin "11") (pinfunction "11_11") (pintype "passive"))
      (node (ref "J5") (pin "11") (pinfunction "11_11") (pintype "passive"))
      (node (ref "J6") (pin "11") (pinfunction "11_11") (pintype "passive"))
      (node (ref "J7") (pin "11") (pinfunction "11_11") (pintype "passive"))
      (node (ref "J8") (pin "11") (pinfunction "11_11") (pintype "passive"))
      (node (ref "J9") (pin "11") (pinfunction "11_11") (pintype "passive"))
    )
    (net (code "159") (name "P5V") (class "Default")
      (node (ref "J10") (pin "13") (pinfunction "13_13") (pintype "passive"))
      (node (ref "J11") (pin "13") (pinfunction "13_13") (pintype "passive"))
      (node (ref "J4") (pin "13") (pinfunction "13_13") (pintype "passive"))
      (node (ref "J5") (pin "13") (pinfunction "13_13") (pintype "passive"))
      (node (ref "J6") (pin "13") (pinfunction "13_13") (pintype "passive"))
      (node (ref "J7") (pin "13") (pinfunction "13_13") (pintype "passive"))
      (node (ref "J8") (pin "13") (pinfunction "13_13") (pintype "passive"))
      (node (ref "J9") (pin "13") (pinfunction "13_13") (pintype "passive"))
    )
    (net (code "160") (name "P9V") (class "Default")
      (node (ref "J10") (pin "14") (pinfunction "14_14") (pintype "passive"))
      (node (ref "J11") (pin "14") (pinfunction "14_14") (pintype "passive"))
      (node (ref "J4") (pin "14") (pinfunction "14_14") (pintype "passive"))
      (node (ref "J5") (pin "14") (pinfunction "14_14") (pintype "passive"))
      (node (ref "J6") (pin "14") (pinfunction "14_14") (pintype "passive"))
      (node (ref "J7") (pin "14") (pinfunction "14_14") (pintype "passive"))
      (node (ref "J8") (pin "14") (pinfunction "14_14") (pintype "passive"))
      (node (ref "J9") (pin "14") (pinfunction "14_14") (pintype "passive"))
    )
    (net (code "161") (name "P12V") (class "Default")
      (node (ref "H10") (pin "2") (pinfunction "2_2") (pintype "passive"))
      (node (ref "H11") (pin "2") (pinfunction "2_2") (pintype "passive"))
      (node (ref "H12") (pin "2") (pinfunction "2_2") (pintype "passive"))
      (node (ref "H5") (pin "2") (pinfunction "2_2") (pintype "passive"))
      (node (ref "H6") (pin "2") (pinfunction "2_2") (pintype "passive"))
      (node (ref "H7") (pin "2") (pinfunction "2_2") (pintype "passive"))
      (node (ref "H8") (pin "2") (pinfunction "2_2") (pintype "passive"))
      (node (ref "H9") (pin "2") (pinfunction "2_2") (pintype "passive"))
    )
  )
)
